# PCIe_Cell_Modem.net
KiCad netlist of a schematic drawn in Altium Designer
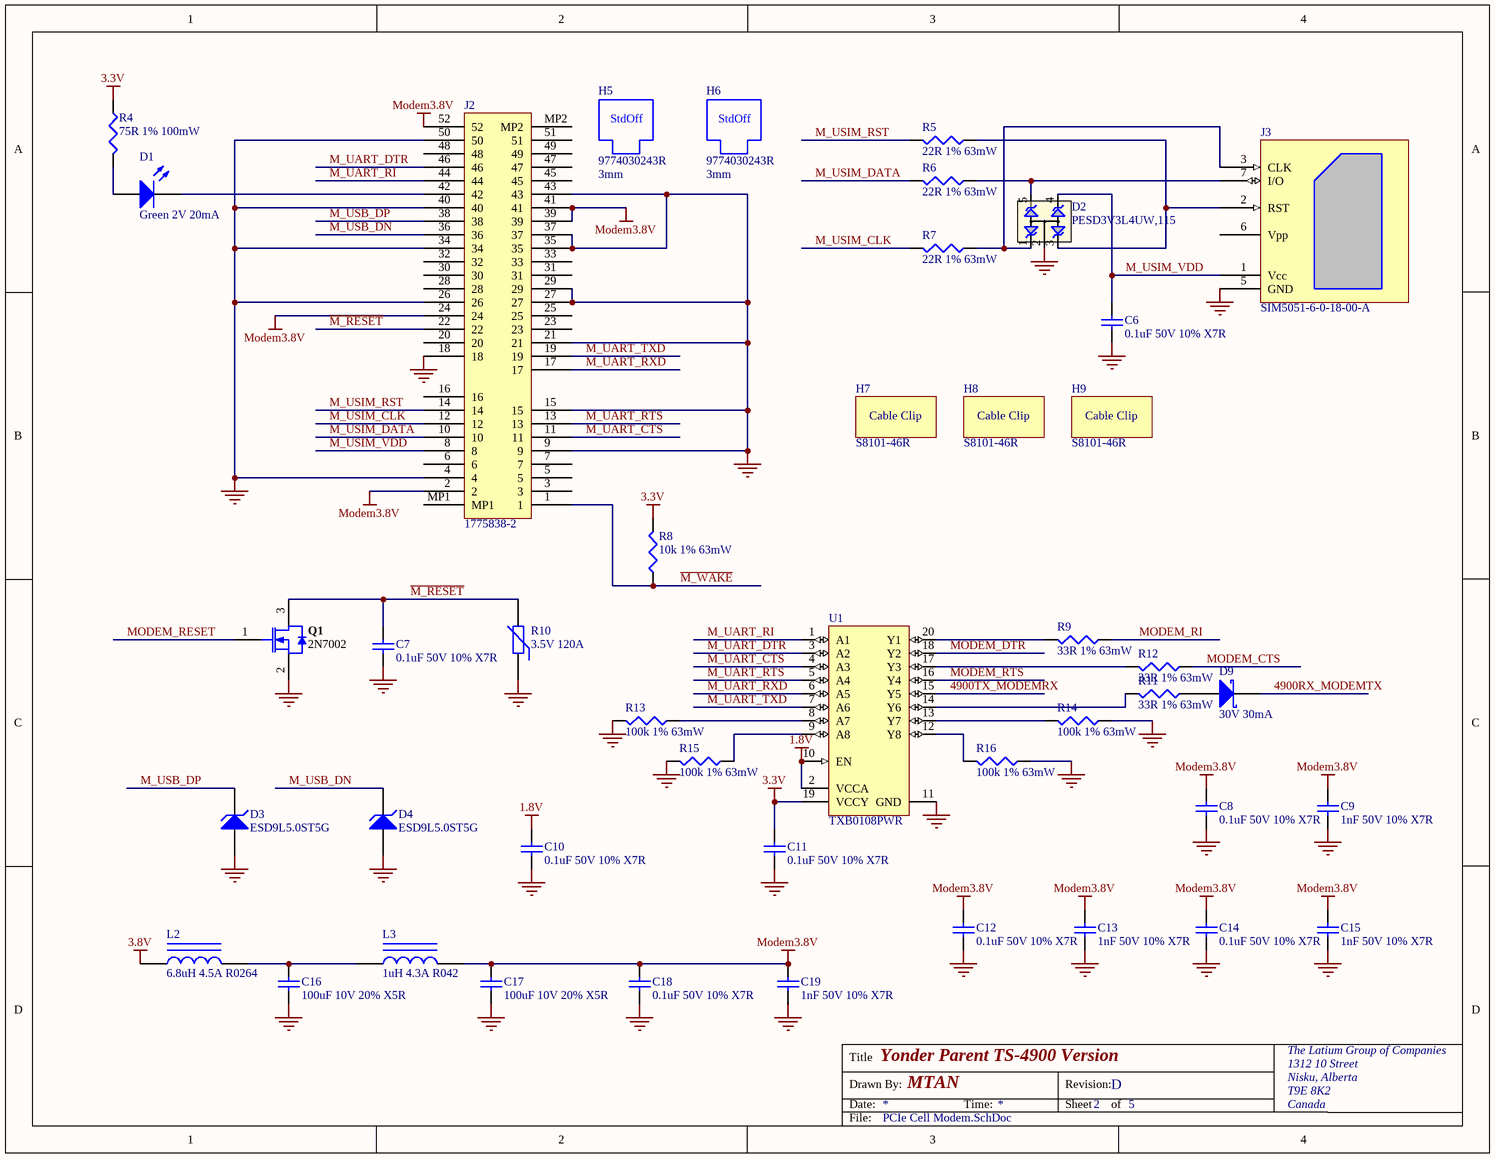
[diagram p0: PCIe Cell Modem.SchDoc]

(export (version "E")
  (design (tool "Eeschema 10.0.6"))
  (components
    (comp (ref "C6")
      (value "0.1uF 50V 10% X7R")
      (footprint "CAPC1005L")
      (description "Capacitor")
      (libsource (lib "Miscellaneous Devices") (part "Cap"))
    )
    (comp (ref "C7")
      (value "0.1uF 50V 10% X7R")
      (footprint "CAPC1005L")
      (description "Capacitor")
      (libsource (lib "Miscellaneous Devices") (part "Cap"))
    )
    (comp (ref "C8")
      (value "0.1uF 50V 10% X7R")
      (footprint "CAPC1005L")
      (description "Capacitor")
      (libsource (lib "Miscellaneous Devices") (part "Cap"))
    )
    (comp (ref "C9")
      (value "1nF 50V 10% X7R")
      (footprint "CAPC1005L")
      (description "Capacitor")
      (libsource (lib "Miscellaneous Devices") (part "Cap"))
    )
    (comp (ref "C10")
      (value "0.1uF 50V 10% X7R")
      (footprint "CAPC1005L")
      (description "Capacitor")
      (libsource (lib "Miscellaneous Devices") (part "Cap"))
    )
    (comp (ref "C11")
      (value "0.1uF 50V 10% X7R")
      (footprint "CAPC1005L")
      (description "Capacitor")
      (libsource (lib "Miscellaneous Devices") (part "Cap"))
    )
    (comp (ref "C12")
      (value "0.1uF 50V 10% X7R")
      (footprint "CAPC1005L")
      (description "Capacitor")
      (libsource (lib "Miscellaneous Devices") (part "Cap"))
    )
    (comp (ref "C13")
      (value "1nF 50V 10% X7R")
      (footprint "CAPC1005L")
      (description "Capacitor")
      (libsource (lib "Miscellaneous Devices") (part "Cap"))
    )
    (comp (ref "C14")
      (value "0.1uF 50V 10% X7R")
      (footprint "CAPC1005L")
      (description "Capacitor")
      (libsource (lib "Miscellaneous Devices") (part "Cap"))
    )
    (comp (ref "C15")
      (value "1nF 50V 10% X7R")
      (footprint "CAPC1005L")
      (description "Capacitor")
      (libsource (lib "Miscellaneous Devices") (part "Cap"))
    )
    (comp (ref "C16")
      (value "100uF 10V 20% X5R")
      (footprint "C1210_L")
      (description "Capacitor")
      (libsource (lib "Miscellaneous Devices") (part "Cap"))
    )
    (comp (ref "C17")
      (value "100uF 10V 20% X5R")
      (footprint "C1210_L")
      (description "Capacitor")
      (libsource (lib "Miscellaneous Devices") (part "Cap"))
    )
    (comp (ref "C18")
      (value "0.1uF 50V 10% X7R")
      (footprint "CAPC1005L")
      (description "Capacitor")
      (libsource (lib "Miscellaneous Devices") (part "Cap"))
    )
    (comp (ref "C19")
      (value "1nF 50V 10% X7R")
      (footprint "CAPC1005L")
      (description "Capacitor")
      (libsource (lib "Miscellaneous Devices") (part "Cap"))
    )
    (comp (ref "D1")
      (value "Green 2V 20mA")
      (footprint "CD1608-0603")
      (description "LED GREEN CLEAR 0603 SMD")
      (fields
        (field (name "MANUFACTURER") "Wurth Electronics Inc")
        (field (name "MANUFACTURER PART NUMBER") "150060VS75000")
      )
      (libsource (lib "Miscellaneous Devices") (part "LED2"))
    )
    (comp (ref "D2")
      (value "PESD3V3L4UW,115")
      (footprint "SOT-665")
      (description "TVS DIODE 3.3V 12V SOT665")
      (fields (field (name "MANUFACTURER") "Nexperia USA Inc"))
      (libsource (lib "WE-TVS TVS Diode-Standard Series") (part "82402374"))
    )
    (comp (ref "D3")
      (value "ESD9L5.0ST5G")
      (footprint "SOD-923")
      (description "TVS DIODE 5V 9.8V SOD923")
      (fields (field (name "MANUFACTURER") "ON Semiconductor"))
      (libsource (lib "Miscellaneous Devices") (part "D Zener"))
    )
    (comp (ref "D4")
      (value "ESD9L5.0ST5G")
      (footprint "SOD-923")
      (description "TVS DIODE 5V 9.8V SOD923")
      (fields (field (name "MANUFACTURER") "ON Semiconductor"))
      (libsource (lib "Miscellaneous Devices") (part "D Zener"))
    )
    (comp (ref "D9")
      (value "30V 30mA")
      (footprint "CD1310-0504")
      (description "DIODE SCHOTTKY 30V 30MA SOD523")
      (fields
        (field (name "MANUFACTURER") "ON Semiconductor")
        (field (name "MANUFACTURER PART NUMBER") "RB751S40T1G")
      )
      (libsource (lib "Miscellaneous Devices") (part "D Schottky"))
    )
    (comp (ref "H5")
      (value "9774030243R")
      (footprint "Wurth 9774030243R")
      (description "ROUND STANDOFF M2X0.4 STEEL 3MM")
      (fields (field (name "MANUFACTURER") "Wurth Electronics Inc") (field (name "HEIGHT") "3mm"))
      (libsource (lib "Latium Component Library") (part "SMD M3 Spacer"))
    )
    (comp (ref "H6")
      (value "9774030243R")
      (footprint "Wurth 9774030243R")
      (description "ROUND STANDOFF M2X0.4 STEEL 3MM")
      (fields (field (name "MANUFACTURER") "Wurth Electronics Inc") (field (name "HEIGHT") "3mm"))
      (libsource (lib "Latium Component Library") (part "SMD M3 Spacer"))
    )
    (comp (ref "H7")
      (value "S8101-46R")
      (footprint "Coax Cable Clip")
      (description "CBL CLIP C-TYPE SILVER SOLDER")
      (fields (field (name "MANUFACTURER") "Harwin Inc"))
      (libsource (lib "Latium Component Library") (part "Cable Clip"))
    )
    (comp (ref "H8")
      (value "S8101-46R")
      (footprint "Coax Cable Clip")
      (description "CBL CLIP C-TYPE SILVER SOLDER")
      (fields (field (name "MANUFACTURER") "Harwin Inc"))
      (libsource (lib "Latium Component Library") (part "Cable Clip"))
    )
    (comp (ref "H9")
      (value "S8101-46R")
      (footprint "Coax Cable Clip")
      (description "CBL CLIP C-TYPE SILVER SOLDER")
      (fields (field (name "MANUFACTURER") "Harwin Inc"))
      (libsource (lib "Latium Component Library") (part "Cable Clip"))
    )
    (comp (ref "J2")
      (value "1775838-2")
      (footprint "TE 1775838-2")
      (description "CONN PCI EXP MINI FEMALE 52POS")
      (fields (field (name "MANUFACTURER") "TE Connectivity AMP Connectors"))
      (libsource (lib "Latium Component Library") (part "TE1775838-2"))
    )
    (comp (ref "J3")
      (value "SIM5051-6-0-18-00-A")
      (footprint "SIM5051-6")
      (description "MINI SIM HINGED, 6P, SMT, 1.8MM")
      (fields (field (name "MANUFACTURER") "GCT"))
      (libsource (lib "Latium Component Library") (part "Mini SIM 6pos Conn"))
    )
    (comp (ref "L2")
      (value "6.8uH 4.5A R0264")
      (footprint "1267AY")
      (description "6.8µH Shielded Fixed Inductor")
      (fields
        (field (name "MANUFACTURER PART NUMBER") "1267AY-6R8N=P3")
        (field (name "MANUFACTURER") "Murata Electronics")
      )
      (libsource (lib "Miscellaneous Devices") (part "Inductor Iron"))
    )
    (comp (ref "L3")
      (value "1uH 4.3A R042")
      (footprint "WE-LQS 252012")
      (description "FIXED IND 1UH 4.3A 42 MOHM SMD")
      (fields
        (field (name "MANUFACTURER PART NUMBER") "DFE252012P-1R0M=P2")
        (field (name "MANUFACTURER") "Murata Electronics")
      )
      (libsource (lib "Miscellaneous Devices") (part "Inductor Iron"))
    )
    (comp (ref "Q1")
      (value "2N7002")
      (footprint "INF-PG-SOT23_L")
      (description "MOSFET N-CH 60V 115MA SOT-23")
      (fields (field (name "MANUFACTURER") "ON Semiconductor"))
      (libsource (lib "Infineon Power MOSFET") (part "2N7002"))
    )
    (comp (ref "R4")
      (value "75R 1% 100mW")
      (footprint "RESC1608L")
      (description "Resistor")
      (libsource (lib "Miscellaneous Devices") (part "Res3"))
    )
    (comp (ref "R5")
      (value "22R 1% 63mW")
      (footprint "RESC1005L")
      (description "Resistor")
      (libsource (lib "Miscellaneous Devices") (part "Res3"))
    )
    (comp (ref "R6")
      (value "22R 1% 63mW")
      (footprint "RESC1005L")
      (description "Resistor")
      (libsource (lib "Miscellaneous Devices") (part "Res3"))
    )
    (comp (ref "R7")
      (value "22R 1% 63mW")
      (footprint "RESC1005L")
      (description "Resistor")
      (libsource (lib "Miscellaneous Devices") (part "Res3"))
    )
    (comp (ref "R8")
      (value "10k 1% 63mW")
      (footprint "RESC1005L")
      (description "Resistor")
      (libsource (lib "Miscellaneous Devices") (part "Res3"))
    )
    (comp (ref "R9")
      (value "33R 1% 63mW")
      (footprint "RESC1005L")
      (description "Resistor")
      (libsource (lib "Miscellaneous Devices") (part "Res3"))
    )
    (comp (ref "R10")
      (value "3.5V 120A")
      (footprint "6-0805_L")
      (description "VARISTOR 5.35V 120A 0805")
      (fields
        (field (name "MANUFACTURER") "Littelfuse Inc")
        (field (name "MANUFACTURER PART NUMBER") "V3.5MLA0805H")
      )
      (libsource (lib "Miscellaneous Devices") (part "Res Varistor"))
    )
    (comp (ref "R11")
      (value "33R 1% 63mW")
      (footprint "RESC1005L")
      (description "Resistor")
      (libsource (lib "Miscellaneous Devices") (part "Res3"))
    )
    (comp (ref "R12")
      (value "33R 1% 63mW")
      (footprint "RESC1005L")
      (description "Resistor")
      (libsource (lib "Miscellaneous Devices") (part "Res3"))
    )
    (comp (ref "R13")
      (value "100k 1% 63mW")
      (footprint "RESC1005L")
      (description "Resistor")
      (libsource (lib "Miscellaneous Devices") (part "Res3"))
    )
    (comp (ref "R14")
      (value "100k 1% 63mW")
      (footprint "RESC1005L")
      (description "Resistor")
      (libsource (lib "Miscellaneous Devices") (part "Res3"))
    )
    (comp (ref "R15")
      (value "100k 1% 63mW")
      (footprint "RESC1005L")
      (description "Resistor")
      (libsource (lib "Miscellaneous Devices") (part "Res3"))
    )
    (comp (ref "R16")
      (value "100k 1% 63mW")
      (footprint "RESC1005L")
      (description "Resistor")
      (libsource (lib "Miscellaneous Devices") (part "Res3"))
    )
    (comp (ref "U1")
      (value "TXB0108PWR")
      (footprint "TSSOP20_L")
      (description "IC TRNSLTR BIDIRECTIONAL 20TSSOP")
      (fields (field (name "MANUFACTURER") "Texas Instruments"))
      (libsource (lib "Analog Devices Interface and Isolation Level Translators") (part "ADG3300BRUZ"))
    )
  )
  (nets
    (net (code "1") (name "/4900RX_MODEMTX") (class "Default")
      (node (ref "D9") (pin "2") (pinfunction "K_2") (pintype "passive"))
    )
    (net (code "2") (name "/4900TX_MODEMRX") (class "Default")
      (node (ref "U1") (pin "15") (pinfunction "Y5_15") (pintype "bidirectional"))
    )
    (net (code "3") (name "/MODEM_CTS") (class "Default")
      (node (ref "R12") (pin "1") (pinfunction "1_1") (pintype "passive"))
    )
    (net (code "4") (name "/MODEM_DTR") (class "Default")
      (node (ref "U1") (pin "18") (pinfunction "Y2_18") (pintype "bidirectional"))
    )
    (net (code "5") (name "/MODEM_RESET") (class "Default")
      (node (ref "Q1") (pin "1") (pinfunction "GATE_1") (pintype "passive"))
    )
    (net (code "6") (name "/MODEM_RI") (class "Default")
      (node (ref "R9") (pin "1") (pinfunction "1_1") (pintype "passive"))
    )
    (net (code "7") (name "/MODEM_RTS") (class "Default")
      (node (ref "U1") (pin "16") (pinfunction "Y4_16") (pintype "bidirectional"))
    )
    (net (code "8") (name "/M_UART_CTS") (class "Default")
      (node (ref "J2") (pin "11") (pinfunction "11_11") (pintype "passive"))
      (node (ref "U1") (pin "4") (pinfunction "A3_4") (pintype "bidirectional"))
    )
    (net (code "9") (name "/M_UART_DTR") (class "Default")
      (node (ref "J2") (pin "46") (pinfunction "46_46") (pintype "passive"))
      (node (ref "U1") (pin "3") (pinfunction "A2_3") (pintype "bidirectional"))
    )
    (net (code "10") (name "/M_UART_RI") (class "Default")
      (node (ref "J2") (pin "44") (pinfunction "44_44") (pintype "passive"))
      (node (ref "U1") (pin "1") (pinfunction "A1_1") (pintype "bidirectional"))
    )
    (net (code "11") (name "/M_UART_RTS") (class "Default")
      (node (ref "J2") (pin "13") (pinfunction "13_13") (pintype "passive"))
      (node (ref "U1") (pin "5") (pinfunction "A4_5") (pintype "bidirectional"))
    )
    (net (code "12") (name "/M_UART_RXD") (class "Default")
      (node (ref "J2") (pin "17") (pinfunction "17_17") (pintype "passive"))
      (node (ref "U1") (pin "6") (pinfunction "A5_6") (pintype "bidirectional"))
    )
    (net (code "13") (name "/M_UART_TXD") (class "Default")
      (node (ref "J2") (pin "19") (pinfunction "19_19") (pintype "passive"))
      (node (ref "U1") (pin "7") (pinfunction "A6_7") (pintype "bidirectional"))
    )
    (net (code "14") (name "/M_USB_DN") (class "Default")
      (node (ref "D4") (pin "2") (pinfunction "K_2") (pintype "passive"))
      (node (ref "J2") (pin "36") (pinfunction "36_36") (pintype "passive"))
    )
    (net (code "15") (name "/M_USB_DP") (class "Default")
      (node (ref "D3") (pin "2") (pinfunction "K_2") (pintype "passive"))
      (node (ref "J2") (pin "38") (pinfunction "38_38") (pintype "passive"))
    )
    (net (code "16") (name "/M_USIM_CLK") (class "Default")
      (node (ref "J2") (pin "12") (pinfunction "12_12") (pintype "passive"))
      (node (ref "R7") (pin "2") (pinfunction "2_2") (pintype "passive"))
    )
    (net (code "17") (name "/M_USIM_DATA") (class "Default")
      (node (ref "J2") (pin "10") (pinfunction "10_10") (pintype "passive"))
      (node (ref "R6") (pin "2") (pinfunction "2_2") (pintype "passive"))
    )
    (net (code "18") (name "/M_USIM_RST") (class "Default")
      (node (ref "J2") (pin "14") (pinfunction "14_14") (pintype "passive"))
      (node (ref "R5") (pin "2") (pinfunction "2_2") (pintype "passive"))
    )
    (net (code "19") (name "/M_USIM_VDD") (class "Default")
      (node (ref "C6") (pin "1") (pinfunction "1_1") (pintype "passive"))
      (node (ref "D2") (pin "4") (pinfunction "C3_4") (pintype "passive"))
      (node (ref "J2") (pin "8") (pinfunction "8_8") (pintype "passive"))
      (node (ref "J3") (pin "1") (pinfunction "Vcc_1") (pintype "power_in"))
    )
    (net (code "20") (name "/~{M_RESET}") (class "Default")
      (node (ref "C7") (pin "1") (pinfunction "1_1") (pintype "passive"))
      (node (ref "J2") (pin "22") (pinfunction "22_22") (pintype "passive"))
      (node (ref "Q1") (pin "3") (pinfunction "DRAIN_3") (pintype "passive"))
      (node (ref "R10") (pin "2") (pinfunction "2_2") (pintype "passive"))
    )
    (net (code "21") (name "/~{M_WAKE}") (class "Default")
      (node (ref "J2") (pin "1") (pinfunction "1_1") (pintype "passive"))
      (node (ref "R8") (pin "1") (pinfunction "1_1") (pintype "passive"))
    )
    (net (code "22") (name "1.8V") (class "Default")
      (node (ref "C10") (pin "1") (pinfunction "1_1") (pintype "passive"))
      (node (ref "U1") (pin "10") (pinfunction "EN_10") (pintype "input"))
      (node (ref "U1") (pin "2") (pinfunction "VCCA_2") (pintype "power_in"))
    )
    (net (code "23") (name "3.3V") (class "Default")
      (node (ref "C11") (pin "1") (pinfunction "1_1") (pintype "passive"))
      (node (ref "R4") (pin "1") (pinfunction "1_1") (pintype "passive"))
      (node (ref "R8") (pin "2") (pinfunction "2_2") (pintype "passive"))
      (node (ref "U1") (pin "19") (pinfunction "VCCY_19") (pintype "power_in"))
    )
    (net (code "24") (name "3.8V") (class "Default")
      (node (ref "L2") (pin "1") (pinfunction "1_1") (pintype "passive"))
    )
    (net (code "25") (name "GND") (class "Default")
      (node (ref "C10") (pin "2") (pinfunction "2_2") (pintype "passive"))
      (node (ref "C11") (pin "2") (pinfunction "2_2") (pintype "passive"))
      (node (ref "C12") (pin "2") (pinfunction "2_2") (pintype "passive"))
      (node (ref "C13") (pin "2") (pinfunction "2_2") (pintype "passive"))
      (node (ref "C14") (pin "2") (pinfunction "2_2") (pintype "passive"))
      (node (ref "C15") (pin "2") (pinfunction "2_2") (pintype "passive"))
      (node (ref "C16") (pin "1") (pinfunction "1_1") (pintype "passive"))
      (node (ref "C17") (pin "1") (pinfunction "1_1") (pintype "passive"))
      (node (ref "C18") (pin "2") (pinfunction "2_2") (pintype "passive"))
      (node (ref "C19") (pin "2") (pinfunction "2_2") (pintype "passive"))
      (node (ref "C6") (pin "2") (pinfunction "2_2") (pintype "passive"))
      (node (ref "C7") (pin "2") (pinfunction "2_2") (pintype "passive"))
      (node (ref "C8") (pin "2") (pinfunction "2_2") (pintype "passive"))
      (node (ref "C9") (pin "2") (pinfunction "2_2") (pintype "passive"))
      (node (ref "D2") (pin "2") (pinfunction "A1_2") (pintype "passive"))
      (node (ref "D3") (pin "1") (pinfunction "A_1") (pintype "passive"))
      (node (ref "D4") (pin "1") (pinfunction "A_1") (pintype "passive"))
      (node (ref "J2") (pin "15") (pinfunction "15_15") (pintype "passive"))
      (node (ref "J2") (pin "18") (pinfunction "18_18") (pintype "passive"))
      (node (ref "J2") (pin "21") (pinfunction "21_21") (pintype "passive"))
      (node (ref "J2") (pin "26") (pinfunction "26_26") (pintype "passive"))
      (node (ref "J2") (pin "27") (pinfunction "27_27") (pintype "passive"))
      (node (ref "J2") (pin "29") (pinfunction "29_29") (pintype "passive"))
      (node (ref "J2") (pin "34") (pinfunction "34_34") (pintype "passive"))
      (node (ref "J2") (pin "35") (pinfunction "35_35") (pintype "passive"))
      (node (ref "J2") (pin "37") (pinfunction "37_37") (pintype "passive"))
      (node (ref "J2") (pin "4") (pinfunction "4_4") (pintype "passive"))
      (node (ref "J2") (pin "40") (pinfunction "40_40") (pintype "passive"))
      (node (ref "J2") (pin "43") (pinfunction "43_43") (pintype "passive"))
      (node (ref "J2") (pin "50") (pinfunction "50_50") (pintype "passive"))
      (node (ref "J2") (pin "9") (pinfunction "9_9") (pintype "passive"))
      (node (ref "J3") (pin "5") (pinfunction "GND_5") (pintype "power_in"))
      (node (ref "Q1") (pin "2") (pinfunction "SOURCE_2") (pintype "passive"))
      (node (ref "R10") (pin "1") (pinfunction "1_1") (pintype "passive"))
      (node (ref "R13") (pin "2") (pinfunction "2_2") (pintype "passive"))
      (node (ref "R14") (pin "1") (pinfunction "1_1") (pintype "passive"))
      (node (ref "R15") (pin "2") (pinfunction "2_2") (pintype "passive"))
      (node (ref "R16") (pin "1") (pinfunction "1_1") (pintype "passive"))
      (node (ref "U1") (pin "11") (pinfunction "GND_11") (pintype "power_in"))
    )
    (net (code "26") (name "Modem3.8V") (class "Default")
      (node (ref "C12") (pin "1") (pinfunction "1_1") (pintype "passive"))
      (node (ref "C13") (pin "1") (pinfunction "1_1") (pintype "passive"))
      (node (ref "C14") (pin "1") (pinfunction "1_1") (pintype "passive"))
      (node (ref "C15") (pin "1") (pinfunction "1_1") (pintype "passive"))
      (node (ref "C17") (pin "2") (pinfunction "2_2") (pintype "passive"))
      (node (ref "C18") (pin "1") (pinfunction "1_1") (pintype "passive"))
      (node (ref "C19") (pin "1") (pinfunction "1_1") (pintype "passive"))
      (node (ref "C8") (pin "1") (pinfunction "1_1") (pintype "passive"))
      (node (ref "C9") (pin "1") (pinfunction "1_1") (pintype "passive"))
      (node (ref "J2") (pin "2") (pinfunction "2_2") (pintype "passive"))
      (node (ref "J2") (pin "24") (pinfunction "24_24") (pintype "passive"))
      (node (ref "J2") (pin "39") (pinfunction "39_39") (pintype "passive"))
      (node (ref "J2") (pin "41") (pinfunction "41_41") (pintype "passive"))
      (node (ref "J2") (pin "52") (pinfunction "52_52") (pintype "passive"))
      (node (ref "L3") (pin "2") (pinfunction "2_2") (pintype "passive"))
    )
    (net (code "27") (name "Net-(C16-Pad2)") (class "Default")
      (node (ref "C16") (pin "2") (pinfunction "2_2") (pintype "passive"))
      (node (ref "L2") (pin "2") (pinfunction "2_2") (pintype "passive"))
      (node (ref "L3") (pin "1") (pinfunction "1_1") (pintype "passive"))
    )
    (net (code "28") (name "Net-(D1-A)") (class "Default")
      (node (ref "D1") (pin "1") (pinfunction "A_1") (pintype "passive"))
      (node (ref "R4") (pin "2") (pinfunction "2_2") (pintype "passive"))
    )
    (net (code "29") (name "Net-(D1-K)") (class "Default")
      (node (ref "D1") (pin "2") (pinfunction "K_2") (pintype "passive"))
      (node (ref "J2") (pin "42") (pinfunction "42_42") (pintype "passive"))
    )
    (net (code "30") (name "Net-(D2-C1)") (class "Default")
      (node (ref "D2") (pin "1") (pinfunction "C1_1") (pintype "passive"))
      (node (ref "J3") (pin "3") (pinfunction "CLK_3") (pintype "input"))
      (node (ref "R7") (pin "1") (pinfunction "1_1") (pintype "passive"))
    )
    (net (code "31") (name "Net-(D2-C2)") (class "Default")
      (node (ref "D2") (pin "3") (pinfunction "C2_3") (pintype "passive"))
      (node (ref "J3") (pin "2") (pinfunction "RST_2") (pintype "input"))
      (node (ref "R5") (pin "1") (pinfunction "1_1") (pintype "passive"))
    )
    (net (code "32") (name "Net-(D2-C4)") (class "Default")
      (node (ref "D2") (pin "5") (pinfunction "C4_5") (pintype "passive"))
      (node (ref "J3") (pin "7") (pinfunction "I/O_7") (pintype "bidirectional"))
      (node (ref "R6") (pin "1") (pinfunction "1_1") (pintype "passive"))
    )
    (net (code "33") (name "Net-(D9-A)") (class "Default")
      (node (ref "D9") (pin "1") (pinfunction "A_1") (pintype "passive"))
      (node (ref "R11") (pin "1") (pinfunction "1_1") (pintype "passive"))
    )
    (net (code "34") (name "Net-(U1-A7)") (class "Default")
      (node (ref "R13") (pin "1") (pinfunction "1_1") (pintype "passive"))
      (node (ref "U1") (pin "8") (pinfunction "A7_8") (pintype "bidirectional"))
    )
    (net (code "35") (name "Net-(U1-A8)") (class "Default")
      (node (ref "R15") (pin "1") (pinfunction "1_1") (pintype "passive"))
      (node (ref "U1") (pin "9") (pinfunction "A8_9") (pintype "bidirectional"))
    )
    (net (code "36") (name "Net-(U1-Y1)") (class "Default")
      (node (ref "R9") (pin "2") (pinfunction "2_2") (pintype "passive"))
      (node (ref "U1") (pin "20") (pinfunction "Y1_20") (pintype "bidirectional"))
    )
    (net (code "37") (name "Net-(U1-Y3)") (class "Default")
      (node (ref "R12") (pin "2") (pinfunction "2_2") (pintype "passive"))
      (node (ref "U1") (pin "17") (pinfunction "Y3_17") (pintype "bidirectional"))
    )
    (net (code "38") (name "Net-(U1-Y6)") (class "Default")
      (node (ref "R11") (pin "2") (pinfunction "2_2") (pintype "passive"))
      (node (ref "U1") (pin "14") (pinfunction "Y6_14") (pintype "bidirectional"))
    )
    (net (code "39") (name "Net-(U1-Y7)") (class "Default")
      (node (ref "R14") (pin "2") (pinfunction "2_2") (pintype "passive"))
      (node (ref "U1") (pin "13") (pinfunction "Y7_13") (pintype "bidirectional"))
    )
    (net (code "40") (name "Net-(U1-Y8)") (class "Default")
      (node (ref "R16") (pin "2") (pinfunction "2_2") (pintype "passive"))
      (node (ref "U1") (pin "12") (pinfunction "Y8_12") (pintype "bidirectional"))
    )
    (net (code "41") (name "unconnected-(J2-Pad3)") (class "Default")
      (node (ref "J2") (pin "3") (pinfunction "3_3") (pintype "passive"))
    )
    (net (code "42") (name "unconnected-(J2-Pad5)") (class "Default")
      (node (ref "J2") (pin "5") (pinfunction "5_5") (pintype "passive"))
    )
    (net (code "43") (name "unconnected-(J2-Pad6)") (class "Default")
      (node (ref "J2") (pin "6") (pinfunction "6_6") (pintype "passive"))
    )
    (net (code "44") (name "unconnected-(J2-Pad7)") (class "Default")
      (node (ref "J2") (pin "7") (pinfunction "7_7") (pintype "passive"))
    )
    (net (code "45") (name "unconnected-(J2-Pad16)") (class "Default")
      (node (ref "J2") (pin "16") (pinfunction "16_16") (pintype "passive"))
    )
    (net (code "46") (name "unconnected-(J2-Pad20)") (class "Default")
      (node (ref "J2") (pin "20") (pinfunction "20_20") (pintype "passive"))
    )
    (net (code "47") (name "unconnected-(J2-Pad23)") (class "Default")
      (node (ref "J2") (pin "23") (pinfunction "23_23") (pintype "passive"))
    )
    (net (code "48") (name "unconnected-(J2-Pad25)") (class "Default")
      (node (ref "J2") (pin "25") (pinfunction "25_25") (pintype "passive"))
    )
    (net (code "49") (name "unconnected-(J2-Pad28)") (class "Default")
      (node (ref "J2") (pin "28") (pinfunction "28_28") (pintype "passive"))
    )
    (net (code "50") (name "unconnected-(J2-Pad30)") (class "Default")
      (node (ref "J2") (pin "30") (pinfunction "30_30") (pintype "passive"))
    )
    (net (code "51") (name "unconnected-(J2-Pad31)") (class "Default")
      (node (ref "J2") (pin "31") (pinfunction "31_31") (pintype "passive"))
    )
    (net (code "52") (name "unconnected-(J2-Pad32)") (class "Default")
      (node (ref "J2") (pin "32") (pinfunction "32_32") (pintype "passive"))
    )
    (net (code "53") (name "unconnected-(J2-Pad33)") (class "Default")
      (node (ref "J2") (pin "33") (pinfunction "33_33") (pintype "passive"))
    )
    (net (code "54") (name "unconnected-(J2-Pad45)") (class "Default")
      (node (ref "J2") (pin "45") (pinfunction "45_45") (pintype "passive"))
    )
    (net (code "55") (name "unconnected-(J2-Pad47)") (class "Default")
      (node (ref "J2") (pin "47") (pinfunction "47_47") (pintype "passive"))
    )
    (net (code "56") (name "unconnected-(J2-Pad48)") (class "Default")
      (node (ref "J2") (pin "48") (pinfunction "48_48") (pintype "passive"))
    )
    (net (code "57") (name "unconnected-(J2-Pad49)") (class "Default")
      (node (ref "J2") (pin "49") (pinfunction "49_49") (pintype "passive"))
    )
    (net (code "58") (name "unconnected-(J2-Pad51)") (class "Default")
      (node (ref "J2") (pin "51") (pinfunction "51_51") (pintype "passive"))
    )
    (net (code "59") (name "unconnected-(J2-PadMP1)") (class "Default")
      (node (ref "J2") (pin "MP1") (pinfunction "MP1_MP1") (pintype "passive"))
    )
    (net (code "60") (name "unconnected-(J2-PadMP2)") (class "Default")
      (node (ref "J2") (pin "MP2") (pinfunction "MP2_MP2") (pintype "passive"))
    )
    (net (code "61") (name "unconnected-(J3-Vpp-Pad6)") (class "Default")
      (node (ref "J3") (pin "6") (pinfunction "Vpp_6") (pintype "passive"))
    )
  )
)
